# CR99001.net
KiCad netlist of a schematic drawn in Altium Designer
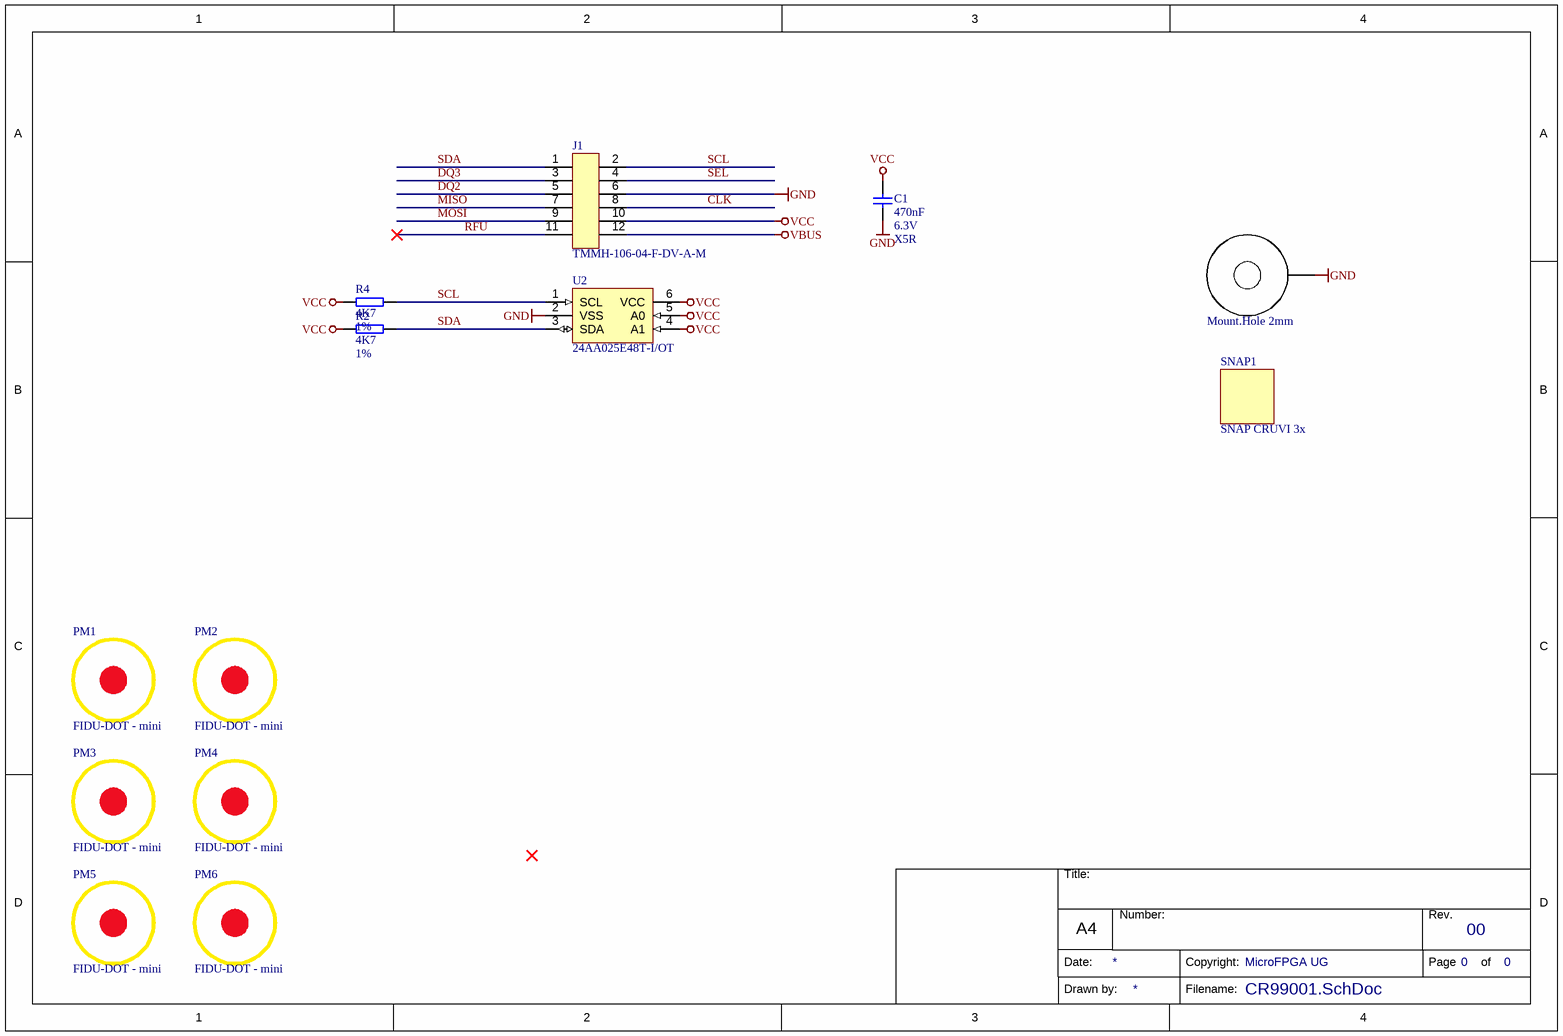
[diagram p0: CR99001.SchDoc]

(export (version "E")
  (design (tool "Eeschema 10.0.6"))
  (components
    (comp (ref "C1")
      (value "470nF")
      (footprint "CAPC1005X55N")
      (description "KON 470nF 6,3V X5R SMD BF 1005 (0402)")
      (fields (field (name "VOLTAGE") "6.3V") (field (name "TECHNOLOGY") "X5R"))
      (libsource (lib "TE") (part "CAP-NP"))
    )
    (comp (ref "H1") (value "Mount.Hole 2mm") (footprint "MHole2_2mm") (libsource (lib "TE") (part "MHole")))
    (comp (ref "J1")
      (value "TMMH-106-04-F-DV-A-M")
      (footprint "TMMH-106-04-T-DV-A")
      (libsource (lib "TE") (part "CON-12"))
    )
    (comp (ref "PM1")
      (value "FIDU-DOT - mini")
      (footprint "FIDU-DOT - mini")
      (description "FIDU-DOT - MINI 0.5mm")
      (libsource (lib "TE") (part "FIDU-DOT - small"))
    )
    (comp (ref "PM2")
      (value "FIDU-DOT - mini")
      (footprint "FIDU-DOT - mini")
      (description "FIDU-DOT - MINI 0.5mm")
      (libsource (lib "TE") (part "FIDU-DOT - small"))
    )
    (comp (ref "PM3")
      (value "FIDU-DOT - mini")
      (footprint "FIDU-DOT - mini")
      (description "FIDU-DOT - MINI 0.5mm")
      (libsource (lib "TE") (part "FIDU-DOT - small"))
    )
    (comp (ref "PM4")
      (value "FIDU-DOT - mini")
      (footprint "FIDU-DOT - mini")
      (description "FIDU-DOT - MINI 0.5mm")
      (libsource (lib "TE") (part "FIDU-DOT - small"))
    )
    (comp (ref "PM5")
      (value "FIDU-DOT - mini")
      (footprint "FIDU-DOT - mini")
      (description "FIDU-DOT - MINI 0.5mm")
      (libsource (lib "TE") (part "FIDU-DOT - small"))
    )
    (comp (ref "PM6")
      (value "FIDU-DOT - mini")
      (footprint "FIDU-DOT - mini")
      (description "FIDU-DOT - MINI 0.5mm")
      (libsource (lib "TE") (part "FIDU-DOT - small"))
    )
    (comp (ref "R2")
      (value "4K7")
      (footprint "RESC1005X40N")
      (description "WID SMD 4K7 1% 0,063W BF 1005 (0402)")
      (fields (field (name "TOLERANCE") "1%"))
      (libsource (lib "TE") (part "RES"))
    )
    (comp (ref "R4")
      (value "4K7")
      (footprint "RESC1005X40N")
      (description "WID SMD 4K7 1% 0,063W BF 1005 (0402)")
      (fields (field (name "TOLERANCE") "1%"))
      (libsource (lib "TE") (part "RES"))
    )
    (comp (ref "SNAP1")
      (value "SNAP CRUVI 3x")
      (footprint "CRUVI_3x_Snap")
      (description "SNAP for CRUVI 3x")
      (libsource (lib "TE") (part "DUMMY"))
    )
    (comp (ref "U2")
      (value "24AA025E48T-I/OT")
      (footprint "SOT95P280X145-6N")
      (libsource (lib "TE") (part "24AA025E48"))
    )
  )
  (nets
    (net (code "1") (name "/CLK") (class "Default")
      (node (ref "J1") (pin "8") (pinfunction "8_8") (pintype "passive"))
    )
    (net (code "2") (name "/DQ2") (class "Default")
      (node (ref "J1") (pin "5") (pinfunction "5_5") (pintype "passive"))
    )
    (net (code "3") (name "/DQ3") (class "Default")
      (node (ref "J1") (pin "3") (pinfunction "3_3") (pintype "passive"))
    )
    (net (code "4") (name "/MISO") (class "Default")
      (node (ref "J1") (pin "7") (pinfunction "7_7") (pintype "passive"))
    )
    (net (code "5") (name "/MOSI") (class "Default")
      (node (ref "J1") (pin "9") (pinfunction "9_9") (pintype "passive"))
    )
    (net (code "6") (name "/RFU") (class "Default")
      (node (ref "J1") (pin "11") (pinfunction "11_11") (pintype "passive+no_connect"))
    )
    (net (code "7") (name "/SCL") (class "Default")
      (node (ref "J1") (pin "2") (pinfunction "2_2") (pintype "passive"))
      (node (ref "R4") (pin "2") (pinfunction "2_2") (pintype "passive"))
      (node (ref "U2") (pin "1") (pinfunction "SCL_1") (pintype "input"))
    )
    (net (code "8") (name "/SDA") (class "Default")
      (node (ref "J1") (pin "1") (pinfunction "1_1") (pintype "passive"))
      (node (ref "R2") (pin "2") (pinfunction "2_2") (pintype "passive"))
      (node (ref "U2") (pin "3") (pinfunction "SDA_3") (pintype "bidirectional"))
    )
    (net (code "9") (name "/SEL") (class "Default")
      (node (ref "J1") (pin "4") (pinfunction "4_4") (pintype "passive"))
    )
    (net (code "10") (name "GND") (class "Default")
      (node (ref "C1") (pin "2") (pinfunction "2_2") (pintype "passive"))
      (node (ref "H1") (pin "1") (pinfunction "1_1") (pintype "passive"))
      (node (ref "J1") (pin "6") (pinfunction "6_6") (pintype "passive"))
      (node (ref "U2") (pin "2") (pinfunction "VSS_2") (pintype "power_in"))
    )
    (net (code "11") (name "VBUS") (class "Default")
      (node (ref "J1") (pin "12") (pinfunction "12_12") (pintype "passive"))
    )
    (net (code "12") (name "VCC") (class "Default")
      (node (ref "C1") (pin "1") (pinfunction "1_1") (pintype "passive"))
      (node (ref "J1") (pin "10") (pinfunction "10_10") (pintype "passive"))
      (node (ref "R2") (pin "1") (pinfunction "1_1") (pintype "passive"))
      (node (ref "R4") (pin "1") (pinfunction "1_1") (pintype "passive"))
      (node (ref "U2") (pin "4") (pinfunction "A1_4") (pintype "input"))
      (node (ref "U2") (pin "5") (pinfunction "A0_5") (pintype "input"))
      (node (ref "U2") (pin "6") (pinfunction "VCC_6") (pintype "power_in"))
    )
  )
)
